# 12_DMIC.net
KiCad netlist of a schematic drawn in Altium Designer
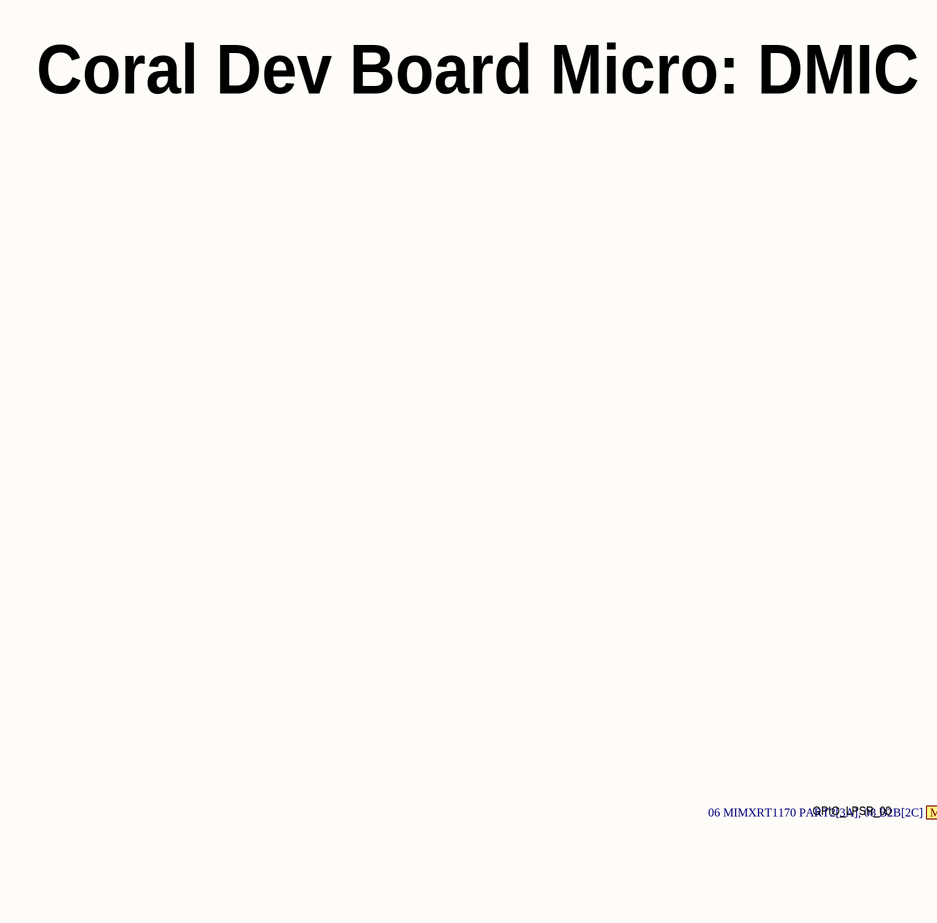
[diagram p0: 12 DMIC.SchDoc, left]
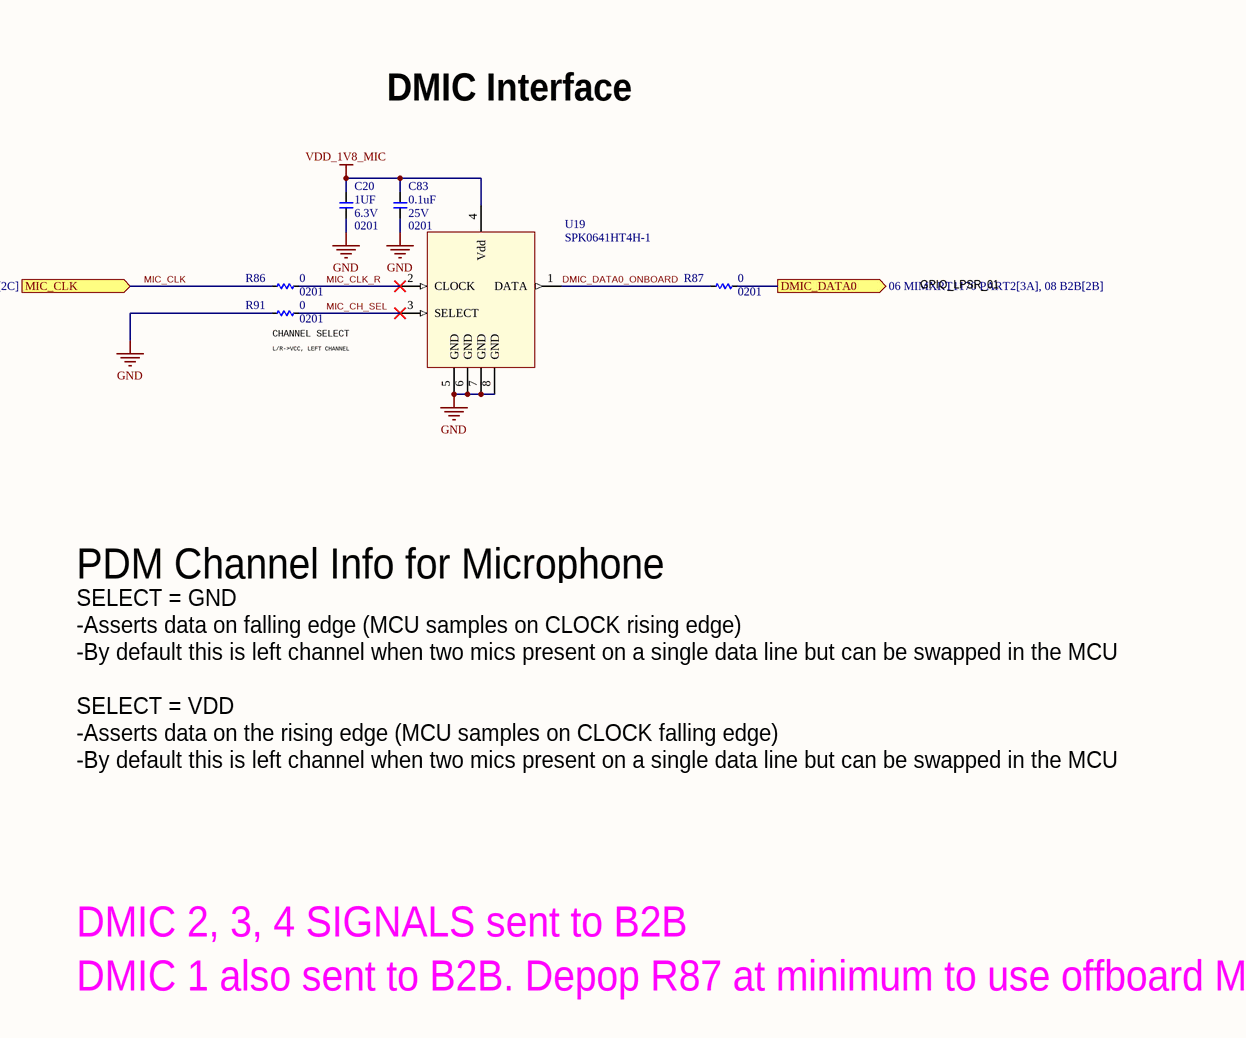
[diagram p1: 12 DMIC.SchDoc, right]

(export (version "E")
  (design (tool "Eeschema 10.0.6"))
  (components
    (comp (ref "C20")
      (value "1UF")
      (footprint "C0201_H0.39MM")
      (description "CAP, CER, X6S, 1uF, 20%, 6.3V, 0201, 0.39mm")
      (fields
        (field (name "MFG") "MURATA")
        (field (name "PACKAGE") "0201")
        (field (name "VOLTAGE") "6.3V")
        (field (name "TOLERANCE") "20%")
      )
      (libsource (lib "AltiumReleaseLibDB") (part "__Template_Cap"))
    )
    (comp (ref "C83")
      (value "0.1uF")
      (footprint "C0201Y")
      (description "CAP, CER, X5R, 0.1uF, 25V, 20%, 0201, 0.33mm T")
      (fields
        (field (name "MFG") "MURATA")
        (field (name "PACKAGE") "0201")
        (field (name "VOLTAGE") "25V")
        (field (name "TOLERANCE") "20%")
      )
      (libsource (lib "AltiumReleaseLibDB") (part "__Template_Cap"))
    )
    (comp (ref "R86")
      (value "0")
      (footprint "R0201")
      (description "RES, 0.0, 1/20W, 0201")
      (fields (field (name "MFG") "PANASONIC") (field (name "PACKAGE") "0201") (field (name "POWER") "1/20W"))
      (libsource (lib "AltiumReleaseLibDB") (part "__Template_Resistor"))
    )
    (comp (ref "R87")
      (value "0")
      (footprint "R0201")
      (description "RES, 0.0, 1/20W, 0201")
      (fields (field (name "MFG") "PANASONIC") (field (name "PACKAGE") "0201") (field (name "POWER") "1/20W"))
      (libsource (lib "AltiumReleaseLibDB") (part "__Template_Resistor"))
    )
    (comp (ref "R91")
      (value "0")
      (footprint "R0201")
      (description "RES, 0.0, 1/20W, 0201")
      (fields (field (name "MFG") "PANASONIC") (field (name "PACKAGE") "0201") (field (name "POWER") "1/20W"))
      (libsource (lib "AltiumReleaseLibDB") (part "__Template_Resistor"))
    )
    (comp (ref "U19")
      (value "MIC_SPK0641HT4H-1")
      (footprint "MIC_SPK0641HT4H-1")
      (fields (field (name "MFG") "Knowles") (field (name "MFG P/N") "SPK0641HT4H-1"))
      (libsource (lib "AltiumReleaseLibDB") (part "MIC_SPK0641HT4H-1"))
    )
  )
  (nets
    (net (code "1") (name "/DMIC_DATA0") (class "Default") (node (ref "R87") (pin "2") (pintype "passive")))
    (net (code "2") (name "/DMIC_DATA0_ONBOARD") (class "Default")
      (node (ref "R87") (pin "1") (pintype "passive"))
      (node (ref "U19") (pin "1") (pinfunction "DATA_1") (pintype "output"))
    )
    (net (code "3") (name "/MIC_CH_SEL") (class "Default")
      (node (ref "R91") (pin "2") (pintype "passive"))
      (node (ref "U19") (pin "3") (pinfunction "SELECT_3") (pintype "input"))
    )
    (net (code "4") (name "/MIC_CLK") (class "Default") (node (ref "R86") (pin "1") (pintype "passive")))
    (net (code "5") (name "/MIC_CLK_R") (class "Default")
      (node (ref "R86") (pin "2") (pintype "passive"))
      (node (ref "U19") (pin "2") (pinfunction "CLOCK_2") (pintype "input"))
    )
    (net (code "6") (name "GND") (class "Default")
      (node (ref "C20") (pin "2") (pintype "passive"))
      (node (ref "C83") (pin "2") (pintype "passive"))
      (node (ref "R91") (pin "1") (pintype "passive"))
      (node (ref "U19") (pin "5") (pinfunction "GND_5") (pintype "power_in"))
      (node (ref "U19") (pin "6") (pinfunction "GND_6") (pintype "power_in"))
      (node (ref "U19") (pin "7") (pinfunction "GND_7") (pintype "power_in"))
      (node (ref "U19") (pin "8") (pinfunction "GND_8") (pintype "power_in"))
    )
    (net (code "7") (name "VDD_1V8_MIC") (class "Default")
      (node (ref "C20") (pin "1") (pintype "passive"))
      (node (ref "C83") (pin "1") (pintype "passive"))
      (node (ref "U19") (pin "4") (pinfunction "Vdd_4") (pintype "power_in"))
    )
  )
)
